# Motor_Controller.net
KiCad netlist of a schematic drawn in Altium Designer
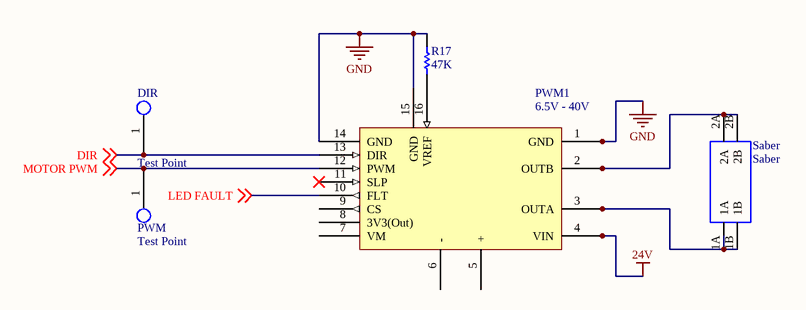
[diagram p0: Motor Controller.SchDoc]

(export (version "E")
  (design (tool "Eeschema 10.0.6"))
  (components
    (comp (ref "DIR")
      (value "Test Point")
      (footprint "Test Point Through-hole")
      (libsource (lib "Husky Robotics Standard Library 2019-2020") (part "Test Point"))
    )
    (comp (ref "PWM")
      (value "Test Point")
      (footprint "Test Point Through-hole")
      (libsource (lib "Husky Robotics Standard Library 2019-2020") (part "Test Point"))
    )
    (comp (ref "PWM1")
      (value "6.5V - 40V")
      (footprint "Pololu_G2_Driver_24v21")
      (libsource (lib "Husky Robotics Standard Library 2019-2020") (part "Pololu G2 High-Power Motor Driver 24v21"))
    )
    (comp (ref "R17")
      (value "47K")
      (footprint "RESC0805(2012)_N")
      (description "120R 0.125W 5% 0805 (2012 Metric)  SMD")
      (fields (field (name "TOLERANCE") "5 %") (field (name "POWER") "0.125 W"))
      (libsource (lib "Husky Robotics Standard Library 2019-2020") (part "120R 5% 0805"))
    )
    (comp (ref "Saber")
      (value "Saber")
      (footprint "Saber")
      (libsource (lib "Husky Robotics Standard Library 2019-2020") (part "Saber"))
    )
  )
  (nets
    (net (code "1") (name "24V") (class "Default")
      (node (ref "PWM1") (pin "4") (pinfunction "VIN_4") (pintype "power_in"))
      (node (ref "PWM1") (pin "4a") (pinfunction "VIN_4a") (pintype "passive"))
      (node (ref "PWM1") (pin "4b") (pinfunction "VIN_4b") (pintype "passive"))
    )
    (net (code "2") (name "DIR") (class "Default")
      (node (ref "DIR") (pin "1") (pinfunction "1_1") (pintype "passive"))
      (node (ref "PWM1") (pin "13") (pinfunction "DIR_13") (pintype "input"))
    )
    (net (code "3") (name "GND") (class "Default")
      (node (ref "PWM1") (pin "1") (pinfunction "GND_1") (pintype "power_in"))
      (node (ref "PWM1") (pin "14") (pinfunction "GND_14") (pintype "power_in"))
      (node (ref "PWM1") (pin "15") (pinfunction "GND_15") (pintype "power_in"))
      (node (ref "PWM1") (pin "1a") (pinfunction "GND_1a") (pintype "passive"))
      (node (ref "PWM1") (pin "1b") (pinfunction "GND_1b") (pintype "passive"))
      (node (ref "R17") (pin "2") (pinfunction "2_2") (pintype "passive"))
    )
    (net (code "4") (name "LED FAULT") (class "Default")
      (node (ref "PWM1") (pin "10") (pinfunction "FLT_10") (pintype "output"))
    )
    (net (code "5") (name "MOTOR PWM") (class "Default")
      (node (ref "PWM") (pin "1") (pinfunction "1_1") (pintype "passive"))
      (node (ref "PWM1") (pin "12") (pinfunction "PWM_12") (pintype "input"))
    )
    (net (code "6") (name "Net-(PWM1-OUTA-Pad3)") (class "Default")
      (node (ref "PWM1") (pin "3") (pinfunction "OUTA_3") (pintype "passive"))
      (node (ref "PWM1") (pin "3a") (pinfunction "OUTA_3a") (pintype "passive"))
      (node (ref "PWM1") (pin "3b") (pinfunction "OUTA_3b") (pintype "power_in"))
      (node (ref "Saber") (pin "1A") (pinfunction "1A_1A") (pintype "passive"))
      (node (ref "Saber") (pin "1B") (pinfunction "1B_1B") (pintype "passive"))
    )
    (net (code "7") (name "Net-(PWM1-OUTB-Pad2)") (class "Default")
      (node (ref "PWM1") (pin "2") (pinfunction "OUTB_2") (pintype "power_in"))
      (node (ref "PWM1") (pin "2a") (pinfunction "OUTB_2a") (pintype "passive"))
      (node (ref "PWM1") (pin "2b") (pinfunction "OUTB_2b") (pintype "passive"))
      (node (ref "Saber") (pin "2A") (pinfunction "2A_2A") (pintype "passive"))
      (node (ref "Saber") (pin "2B") (pinfunction "2B_2B") (pintype "passive"))
    )
    (net (code "8") (name "Net-(PWM1-VREF)") (class "Default")
      (node (ref "PWM1") (pin "16") (pinfunction "VREF_16") (pintype "input"))
      (node (ref "R17") (pin "1") (pinfunction "1_1") (pintype "passive"))
    )
    (net (code "9") (name "unconnected-(PWM1-+-Pad5)") (class "Default")
      (node (ref "PWM1") (pin "5") (pinfunction "+_5") (pintype "power_in"))
    )
    (net (code "10") (name "unconnected-(PWM1---Pad6)") (class "Default")
      (node (ref "PWM1") (pin "6") (pinfunction "-_6") (pintype "power_in"))
    )
    (net (code "11") (name "unconnected-(PWM1-3V3(Out)-Pad8)") (class "Default")
      (node (ref "PWM1") (pin "8") (pinfunction "3V3(Out)_8") (pintype "power_in"))
    )
    (net (code "12") (name "unconnected-(PWM1-CS-Pad9)") (class "Default")
      (node (ref "PWM1") (pin "9") (pinfunction "CS_9") (pintype "output"))
    )
    (net (code "13") (name "unconnected-(PWM1-SLP-Pad11)") (class "Default")
      (node (ref "PWM1") (pin "11") (pinfunction "SLP_11") (pintype "input+no_connect"))
    )
    (net (code "14") (name "unconnected-(PWM1-VM-Pad7)") (class "Default")
      (node (ref "PWM1") (pin "7") (pinfunction "VM_7") (pintype "power_in"))
    )
  )
)
